# simon_shield.net
KiCad netlist of a schematic drawn in EAGLE
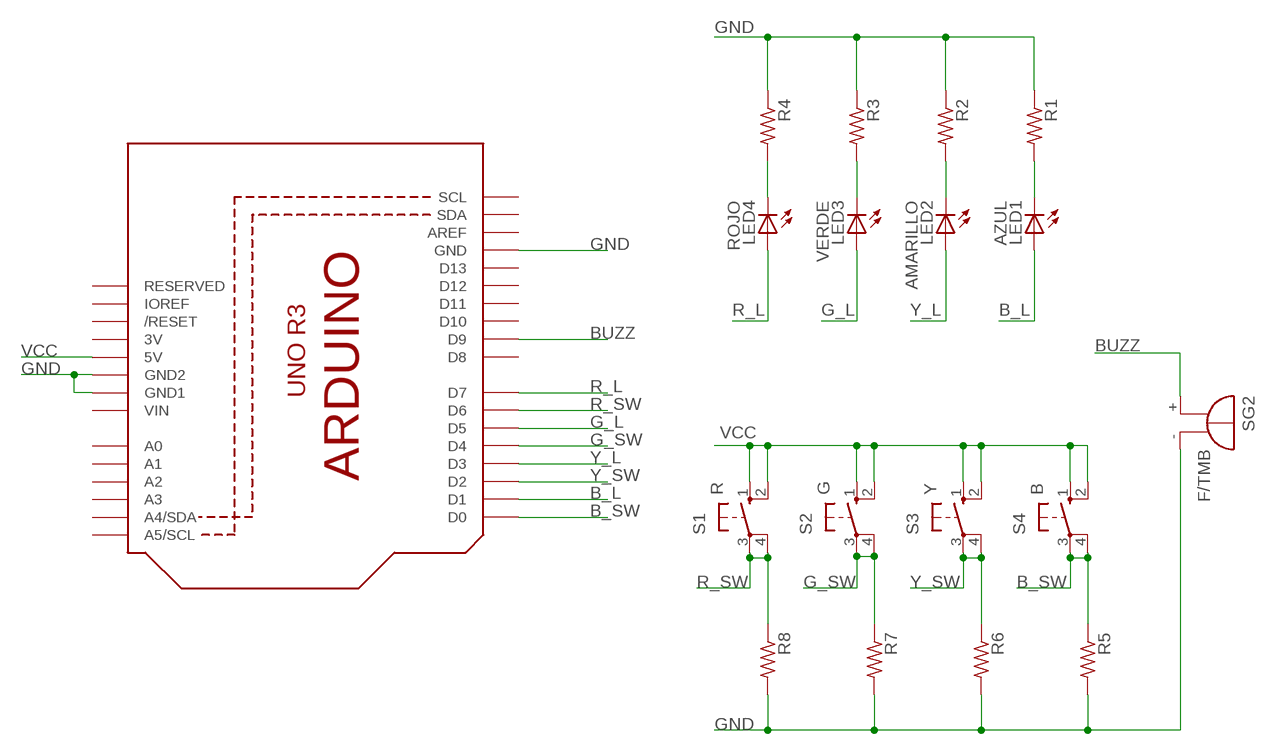
[diagram p0: schematic, sheet 1]

(export (version "E")
  (design (tool "Eeschema 10.0.6"))
  (components
    (comp (ref "LED1")
      (value "AZUL")
      (footprint "eagle-import:LED5MM")
      (libsource (lib "eagle-import") (part "LED5MM"))
    )
    (comp (ref "LED2")
      (value "AMARILLO")
      (footprint "eagle-import:LED5MM")
      (libsource (lib "eagle-import") (part "LED5MM"))
    )
    (comp (ref "LED3")
      (value "VERDE")
      (footprint "eagle-import:LED5MM")
      (libsource (lib "eagle-import") (part "LED5MM"))
    )
    (comp (ref "LED4")
      (value "ROJO")
      (footprint "eagle-import:LED5MM")
      (libsource (lib "eagle-import") (part "LED5MM"))
    )
    (comp (ref "R1")
      (value "R-US_0207/10")
      (footprint "eagle-import:0207_10")
      (libsource (lib "eagle-import") (part "R-US_0207/10"))
    )
    (comp (ref "R2")
      (value "R-US_0207/10")
      (footprint "eagle-import:0207_10")
      (libsource (lib "eagle-import") (part "R-US_0207/10"))
    )
    (comp (ref "R3")
      (value "R-US_0207/10")
      (footprint "eagle-import:0207_10")
      (libsource (lib "eagle-import") (part "R-US_0207/10"))
    )
    (comp (ref "R4")
      (value "R-US_0207/10")
      (footprint "eagle-import:0207_10")
      (libsource (lib "eagle-import") (part "R-US_0207/10"))
    )
    (comp (ref "R5")
      (value "R-US_0207/10")
      (footprint "eagle-import:0207_10")
      (libsource (lib "eagle-import") (part "R-US_0207/10"))
    )
    (comp (ref "R6")
      (value "R-US_0207/10")
      (footprint "eagle-import:0207_10")
      (libsource (lib "eagle-import") (part "R-US_0207/10"))
    )
    (comp (ref "R7")
      (value "R-US_0207/10")
      (footprint "eagle-import:0207_10")
      (libsource (lib "eagle-import") (part "R-US_0207/10"))
    )
    (comp (ref "R8")
      (value "R-US_0207/10")
      (footprint "eagle-import:0207_10")
      (libsource (lib "eagle-import") (part "R-US_0207/10"))
    )
    (comp (ref "S1")
      (value "R")
      (footprint "eagle-import:B3F-10XX")
      (fields (field (name "MPN") "B3F-1000"))
      (libsource (lib "eagle-import") (part "10-XX"))
    )
    (comp (ref "S2")
      (value "G")
      (footprint "eagle-import:B3F-10XX")
      (fields (field (name "MPN") "B3F-1000"))
      (libsource (lib "eagle-import") (part "10-XX"))
    )
    (comp (ref "S3")
      (value "Y")
      (footprint "eagle-import:B3F-10XX")
      (fields (field (name "MPN") "B3F-1000"))
      (libsource (lib "eagle-import") (part "10-XX"))
    )
    (comp (ref "S4")
      (value "B")
      (footprint "eagle-import:B3F-10XX")
      (fields (field (name "MPN") "B3F-1000"))
      (libsource (lib "eagle-import") (part "10-XX"))
    )
    (comp (ref "SG2")
      (value "F/TMB")
      (footprint "eagle-import:F_TMB")
      (libsource (lib "eagle-import") (part "F/TMB"))
    )
    (comp (ref "U1")
      (value "ARDUINOR3-DIMENSION")
      (footprint "eagle-import:ARDUINOR3")
      (libsource (lib "eagle-import") (part "ARDUINOR3-DIMENSION"))
    )
  )
  (nets
    (net (code "1") (name "/3V") (class "Default")
      (node (ref "U1") (pin "3V") (pinfunction "3V_3V") (pintype "power_in"))
    )
    (net (code "2") (name "/BUZZ") (class "Default")
      (node (ref "SG2") (pin "+") (pinfunction "+_+") (pintype "passive"))
      (node (ref "U1") (pin "D9") (pinfunction "D9_D9") (pintype "bidirectional"))
    )
    (net (code "3") (name "/B_L") (class "Default")
      (node (ref "LED1") (pin "A") (pinfunction "A_A") (pintype "passive"))
      (node (ref "U1") (pin "D1") (pinfunction "D1_D1") (pintype "bidirectional"))
    )
    (net (code "4") (name "/B_SW") (class "Default")
      (node (ref "R5") (pin "1") (pinfunction "1_1") (pintype "passive"))
      (node (ref "S4") (pin "3") (pinfunction "P_3") (pintype "passive"))
      (node (ref "S4") (pin "4") (pinfunction "P1_4") (pintype "passive"))
      (node (ref "U1") (pin "D0") (pinfunction "D0_D0") (pintype "bidirectional"))
    )
    (net (code "5") (name "/GND") (class "Default")
      (node (ref "R1") (pin "1") (pinfunction "1_1") (pintype "passive"))
      (node (ref "R2") (pin "1") (pinfunction "1_1") (pintype "passive"))
      (node (ref "R3") (pin "1") (pinfunction "1_1") (pintype "passive"))
      (node (ref "R4") (pin "1") (pinfunction "1_1") (pintype "passive"))
      (node (ref "R5") (pin "2") (pinfunction "2_2") (pintype "passive"))
      (node (ref "R6") (pin "2") (pinfunction "2_2") (pintype "passive"))
      (node (ref "R7") (pin "2") (pinfunction "2_2") (pintype "passive"))
      (node (ref "R8") (pin "2") (pinfunction "2_2") (pintype "passive"))
      (node (ref "SG2") (pin "-") (pinfunction "-_-") (pintype "passive"))
      (node (ref "U1") (pin "GND") (pinfunction "GND_GND") (pintype "power_in"))
      (node (ref "U1") (pin "GND1") (pinfunction "GND1_GND1") (pintype "power_in"))
      (node (ref "U1") (pin "GND2") (pinfunction "GND2_GND2") (pintype "power_in"))
    )
    (net (code "6") (name "/G_L") (class "Default")
      (node (ref "LED3") (pin "A") (pinfunction "A_A") (pintype "passive"))
      (node (ref "U1") (pin "D5") (pinfunction "D5_D5") (pintype "bidirectional"))
    )
    (net (code "7") (name "/G_SW") (class "Default")
      (node (ref "R7") (pin "1") (pinfunction "1_1") (pintype "passive"))
      (node (ref "S2") (pin "3") (pinfunction "P_3") (pintype "passive"))
      (node (ref "S2") (pin "4") (pinfunction "P1_4") (pintype "passive"))
      (node (ref "U1") (pin "D4") (pinfunction "D4_D4") (pintype "bidirectional"))
    )
    (net (code "8") (name "/R_L") (class "Default")
      (node (ref "LED4") (pin "A") (pinfunction "A_A") (pintype "passive"))
      (node (ref "U1") (pin "D7") (pinfunction "D7_D7") (pintype "bidirectional"))
    )
    (net (code "9") (name "/R_SW") (class "Default")
      (node (ref "R8") (pin "1") (pinfunction "1_1") (pintype "passive"))
      (node (ref "S1") (pin "3") (pinfunction "P_3") (pintype "passive"))
      (node (ref "S1") (pin "4") (pinfunction "P1_4") (pintype "passive"))
      (node (ref "U1") (pin "D6") (pinfunction "D6_D6") (pintype "bidirectional"))
    )
    (net (code "10") (name "/VCC") (class "Default")
      (node (ref "S1") (pin "1") (pinfunction "S_1") (pintype "passive"))
      (node (ref "S1") (pin "2") (pinfunction "S1_2") (pintype "passive"))
      (node (ref "S2") (pin "1") (pinfunction "S_1") (pintype "passive"))
      (node (ref "S2") (pin "2") (pinfunction "S1_2") (pintype "passive"))
      (node (ref "S3") (pin "1") (pinfunction "S_1") (pintype "passive"))
      (node (ref "S3") (pin "2") (pinfunction "S1_2") (pintype "passive"))
      (node (ref "S4") (pin "1") (pinfunction "S_1") (pintype "passive"))
      (node (ref "S4") (pin "2") (pinfunction "S1_2") (pintype "passive"))
      (node (ref "U1") (pin "5V") (pinfunction "5V_5V") (pintype "power_in"))
    )
    (net (code "11") (name "/VIN") (class "Default")
      (node (ref "U1") (pin "VIN") (pinfunction "VIN_VIN") (pintype "power_in"))
    )
    (net (code "12") (name "/Y_L") (class "Default")
      (node (ref "LED2") (pin "A") (pinfunction "A_A") (pintype "passive"))
      (node (ref "U1") (pin "D3") (pinfunction "D3_D3") (pintype "bidirectional"))
    )
    (net (code "13") (name "/Y_SW") (class "Default")
      (node (ref "R6") (pin "1") (pinfunction "1_1") (pintype "passive"))
      (node (ref "S3") (pin "3") (pinfunction "P_3") (pintype "passive"))
      (node (ref "S3") (pin "4") (pinfunction "P1_4") (pintype "passive"))
      (node (ref "U1") (pin "D2") (pinfunction "D2_D2") (pintype "bidirectional"))
    )
    (net (code "14") (name "Net-(LED1-C)") (class "Default")
      (node (ref "LED1") (pin "K") (pinfunction "C_K") (pintype "passive"))
      (node (ref "R1") (pin "2") (pinfunction "2_2") (pintype "passive"))
    )
    (net (code "15") (name "Net-(LED2-C)") (class "Default")
      (node (ref "LED2") (pin "K") (pinfunction "C_K") (pintype "passive"))
      (node (ref "R2") (pin "2") (pinfunction "2_2") (pintype "passive"))
    )
    (net (code "16") (name "Net-(LED3-C)") (class "Default")
      (node (ref "LED3") (pin "K") (pinfunction "C_K") (pintype "passive"))
      (node (ref "R3") (pin "2") (pinfunction "2_2") (pintype "passive"))
    )
    (net (code "17") (name "Net-(LED4-C)") (class "Default")
      (node (ref "LED4") (pin "K") (pinfunction "C_K") (pintype "passive"))
      (node (ref "R4") (pin "2") (pinfunction "2_2") (pintype "passive"))
    )
    (net (code "18") (name "unconnected-(U1-A4{slash}SDA-PadA4)") (class "Default")
      (node (ref "U1") (pin "A4") (pinfunction "A4/SDA_A4") (pintype "bidirectional"))
    )
    (net (code "19") (name "unconnected-(U1-A5{slash}SCL-PadA5)") (class "Default")
      (node (ref "U1") (pin "A5") (pinfunction "A5/SCL_A5") (pintype "bidirectional"))
    )
    (net (code "20") (name "unconnected-(U1-PadA0)") (class "Default")
      (node (ref "U1") (pin "A0") (pinfunction "A0_A0") (pintype "bidirectional"))
    )
    (net (code "21") (name "unconnected-(U1-PadA1)") (class "Default")
      (node (ref "U1") (pin "A1") (pinfunction "A1_A1") (pintype "bidirectional"))
    )
    (net (code "22") (name "unconnected-(U1-PadA2)") (class "Default")
      (node (ref "U1") (pin "A2") (pinfunction "A2_A2") (pintype "bidirectional"))
    )
    (net (code "23") (name "unconnected-(U1-PadA3)") (class "Default")
      (node (ref "U1") (pin "A3") (pinfunction "A3_A3") (pintype "bidirectional"))
    )
    (net (code "24") (name "unconnected-(U1-PadAREF)") (class "Default")
      (node (ref "U1") (pin "AREF") (pinfunction "AREF_AREF") (pintype "bidirectional"))
    )
    (net (code "25") (name "unconnected-(U1-PadD8)") (class "Default")
      (node (ref "U1") (pin "D8") (pinfunction "D8_D8") (pintype "bidirectional"))
    )
    (net (code "26") (name "unconnected-(U1-PadD10)") (class "Default")
      (node (ref "U1") (pin "D10") (pinfunction "D10_D10") (pintype "bidirectional"))
    )
    (net (code "27") (name "unconnected-(U1-PadD11)") (class "Default")
      (node (ref "U1") (pin "D11") (pinfunction "D11_D11") (pintype "bidirectional"))
    )
    (net (code "28") (name "unconnected-(U1-PadD12)") (class "Default")
      (node (ref "U1") (pin "D12") (pinfunction "D12_D12") (pintype "bidirectional"))
    )
    (net (code "29") (name "unconnected-(U1-PadD13)") (class "Default")
      (node (ref "U1") (pin "D13") (pinfunction "D13_D13") (pintype "bidirectional"))
    )
    (net (code "30") (name "unconnected-(U1-PadIOREF)") (class "Default")
      (node (ref "U1") (pin "IOREF") (pinfunction "IOREF_IOREF") (pintype "output"))
    )
    (net (code "31") (name "unconnected-(U1-PadRESERVED)") (class "Default")
      (node (ref "U1") (pin "RESERVED") (pinfunction "RESERVED_RESERVED") (pintype "no_connect"))
    )
    (net (code "32") (name "unconnected-(U1-PadSCL)") (class "Default")
      (node (ref "U1") (pin "SCL") (pinfunction "SCL_SCL") (pintype "bidirectional"))
    )
    (net (code "33") (name "unconnected-(U1-PadSDA)") (class "Default")
      (node (ref "U1") (pin "SDA") (pinfunction "SDA_SDA") (pintype "bidirectional"))
    )
    (net (code "34") (name "unconnected-(U1-{slash}RESET-PadRESET)") (class "Default")
      (node (ref "U1") (pin "RESET") (pinfunction "/RESET_RESET") (pintype "bidirectional"))
    )
  )
)
